# ISO.net
KiCad netlist of a schematic drawn in Altium Designer
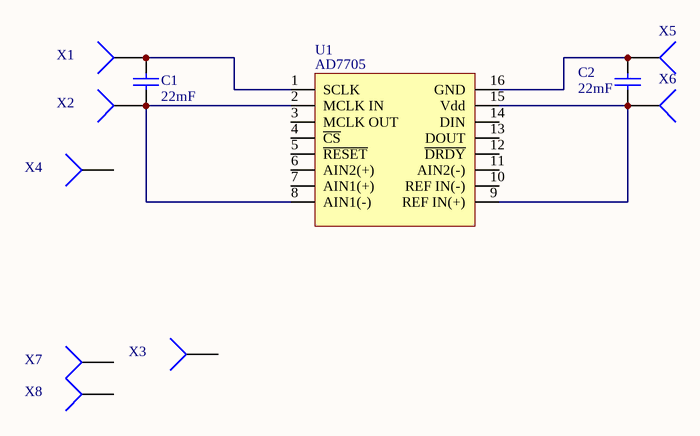
[diagram p0: ISO.SchDoc]

(export (version "E")
  (design (tool "Eeschema 10.0.6"))
  (components
    (comp (ref "C1")
      (value "22mF")
      (footprint "C3216-1206")
      (description "Capacitor (Semiconductor SIM Model)")
      (fields (field (name "MANUFACTURER") "Generic Components") (field (name "PUBLISHER") "Altium Limited"))
      (libsource (lib "Miscellaneous Devices") (part "Cap Semi"))
    )
    (comp (ref "C2")
      (value "22mF")
      (footprint "C3216-1206")
      (description "Capacitor (Semiconductor SIM Model)")
      (fields (field (name "MANUFACTURER") "Generic Components") (field (name "PUBLISHER") "Altium Limited"))
      (libsource (lib "Miscellaneous Devices") (part "Cap Semi"))
    )
    (comp (ref "U1")
      (value "AD7705")
      (footprint "SO-G16/D10.4")
      (description "ADC")
      (libsource (lib "PAL") (part "AD7705"))
    )
    (comp (ref "X1")
      (value "~")
      (footprint "PIN1")
      (description "Socket")
      (fields (field (name "MANUFACTURER") "Generic Components") (field (name "PUBLISHER") "Altium Limited"))
      (libsource (lib "Miscellaneous Connectors") (part "Socket"))
    )
    (comp (ref "X2")
      (value "~")
      (footprint "PIN1")
      (description "Socket")
      (fields (field (name "MANUFACTURER") "Generic Components") (field (name "PUBLISHER") "Altium Limited"))
      (libsource (lib "Miscellaneous Connectors") (part "Socket"))
    )
    (comp (ref "X3")
      (value "~")
      (footprint "PIN1")
      (description "Socket")
      (fields (field (name "MANUFACTURER") "Generic Components") (field (name "PUBLISHER") "Altium Limited"))
      (libsource (lib "Miscellaneous Connectors") (part "Socket"))
    )
    (comp (ref "X4")
      (value "~")
      (footprint "PIN1")
      (description "Socket")
      (fields (field (name "MANUFACTURER") "Generic Components") (field (name "PUBLISHER") "Altium Limited"))
      (libsource (lib "Miscellaneous Connectors") (part "Socket"))
    )
    (comp (ref "X5")
      (value "~")
      (footprint "PIN1")
      (description "Socket")
      (fields (field (name "MANUFACTURER") "Generic Components") (field (name "PUBLISHER") "Altium Limited"))
      (libsource (lib "Miscellaneous Connectors") (part "Socket"))
    )
    (comp (ref "X6")
      (value "~")
      (footprint "PIN1")
      (description "Socket")
      (fields (field (name "MANUFACTURER") "Generic Components") (field (name "PUBLISHER") "Altium Limited"))
      (libsource (lib "Miscellaneous Connectors") (part "Socket"))
    )
    (comp (ref "X7")
      (value "~")
      (footprint "PIN1")
      (description "Socket")
      (fields (field (name "MANUFACTURER") "Generic Components") (field (name "PUBLISHER") "Altium Limited"))
      (libsource (lib "Miscellaneous Connectors") (part "Socket"))
    )
    (comp (ref "X8")
      (value "~")
      (footprint "PIN1")
      (description "Socket")
      (fields (field (name "MANUFACTURER") "Generic Components") (field (name "PUBLISHER") "Altium Limited"))
      (libsource (lib "Miscellaneous Connectors") (part "Socket"))
    )
  )
  (nets
    (net (code "1") (name "Net-(U1-AIN1(-))") (class "Default")
      (node (ref "C1") (pin "1") (pinfunction "1_1") (pintype "passive"))
      (node (ref "U1") (pin "2") (pinfunction "MCLK_IN_2") (pintype "passive"))
      (node (ref "U1") (pin "8") (pinfunction "AIN1(-)_8") (pintype "passive"))
      (node (ref "X2") (pin "1") (pinfunction "1_1") (pintype "passive"))
    )
    (net (code "2") (name "Net-(U1-GND)") (class "Default")
      (node (ref "C2") (pin "2") (pinfunction "2_2") (pintype "passive"))
      (node (ref "U1") (pin "16") (pinfunction "GND_16") (pintype "passive"))
      (node (ref "X5") (pin "1") (pinfunction "1_1") (pintype "passive"))
    )
    (net (code "3") (name "Net-(U1-REF_IN(+))") (class "Default")
      (node (ref "C2") (pin "1") (pinfunction "1_1") (pintype "passive"))
      (node (ref "U1") (pin "15") (pinfunction "Vdd_15") (pintype "passive"))
      (node (ref "U1") (pin "9") (pinfunction "REF_IN(+)_9") (pintype "passive"))
      (node (ref "X6") (pin "1") (pinfunction "1_1") (pintype "passive"))
    )
    (net (code "4") (name "Net-(U1-SCLK)") (class "Default")
      (node (ref "C1") (pin "2") (pinfunction "2_2") (pintype "passive"))
      (node (ref "U1") (pin "1") (pinfunction "SCLK_1") (pintype "passive"))
      (node (ref "X1") (pin "1") (pinfunction "1_1") (pintype "passive"))
    )
    (net (code "5") (name "unconnected-(U1-AIN1(+)-Pad7)") (class "Default")
      (node (ref "U1") (pin "7") (pinfunction "AIN1(+)_7") (pintype "passive"))
    )
    (net (code "6") (name "unconnected-(U1-AIN2(+)-Pad6)") (class "Default")
      (node (ref "U1") (pin "6") (pinfunction "AIN2(+)_6") (pintype "passive"))
    )
    (net (code "7") (name "unconnected-(U1-AIN2(-)-Pad11)") (class "Default")
      (node (ref "U1") (pin "11") (pinfunction "AIN2(-)_11") (pintype "passive"))
    )
    (net (code "8") (name "unconnected-(U1-DIN-Pad14)") (class "Default")
      (node (ref "U1") (pin "14") (pinfunction "DIN_14") (pintype "passive"))
    )
    (net (code "9") (name "unconnected-(U1-DOUT-Pad13)") (class "Default")
      (node (ref "U1") (pin "13") (pinfunction "DOUT_13") (pintype "passive"))
    )
    (net (code "10") (name "unconnected-(U1-MCLK_OUT-Pad3)") (class "Default")
      (node (ref "U1") (pin "3") (pinfunction "MCLK_OUT_3") (pintype "passive"))
    )
    (net (code "11") (name "unconnected-(U1-REF_IN(-)-Pad10)") (class "Default")
      (node (ref "U1") (pin "10") (pinfunction "REF_IN(-)_10") (pintype "passive"))
    )
    (net (code "12") (name "unconnected-(U1-~{CS}-Pad4)") (class "Default")
      (node (ref "U1") (pin "4") (pinfunction "~{CS}_4") (pintype "passive"))
    )
    (net (code "13") (name "unconnected-(U1-~{DRDY}-Pad12)") (class "Default")
      (node (ref "U1") (pin "12") (pinfunction "~{DRDY}_12") (pintype "passive"))
    )
    (net (code "14") (name "unconnected-(U1-~{RESET}-Pad5)") (class "Default")
      (node (ref "U1") (pin "5") (pinfunction "~{RESET}_5") (pintype "passive"))
    )
    (net (code "15") (name "unconnected-(X3-Pad1)") (class "Default")
      (node (ref "X3") (pin "1") (pinfunction "1_1") (pintype "passive"))
    )
    (net (code "16") (name "unconnected-(X4-Pad1)") (class "Default")
      (node (ref "X4") (pin "1") (pinfunction "1_1") (pintype "passive"))
    )
    (net (code "17") (name "unconnected-(X7-Pad1)") (class "Default")
      (node (ref "X7") (pin "1") (pinfunction "1_1") (pintype "passive"))
    )
    (net (code "18") (name "unconnected-(X8-Pad1)") (class "Default")
      (node (ref "X8") (pin "1") (pinfunction "1_1") (pintype "passive"))
    )
  )
)
